# LB-word-topLevel.net
KiCad netlist of a schematic drawn in Altium Designer
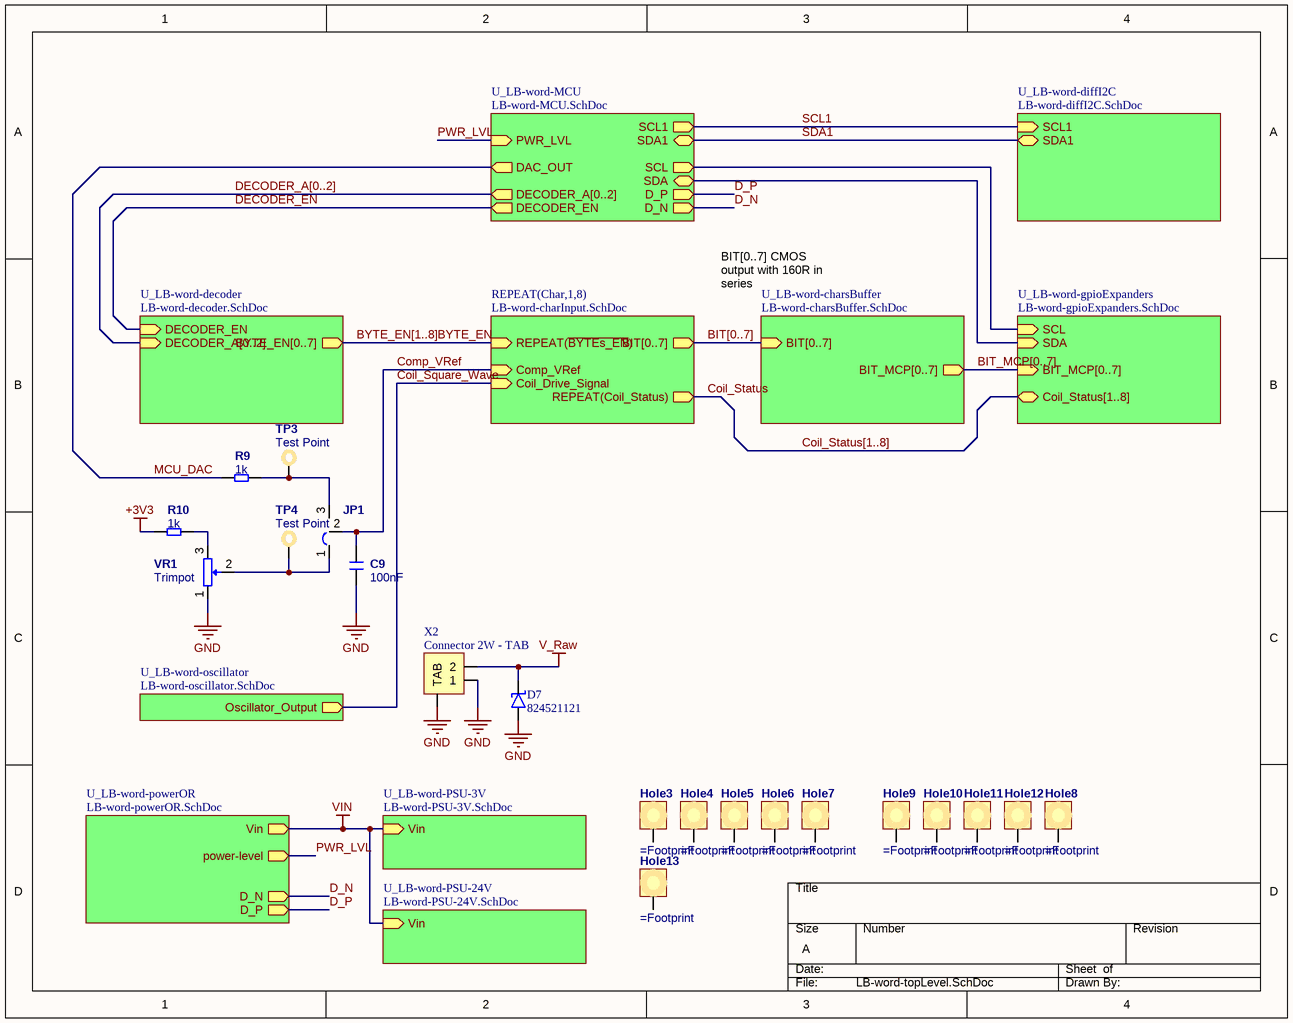
[diagram p0: LB-word-topLevel.SchDoc]

(export (version "E")
  (design (tool "Eeschema 10.0.6"))
  (components
    (comp (ref "C9")
      (value "100nF")
      (footprint "C0603_N")
      (description "Capacitor MLCC")
      (fields
        (field (name "MANUFACTURER") "Yageo")
        (field (name "MANUFACTURER PART NUMBER") "CC0603KRX7R9BB104")
      )
      (libsource (lib "wes") (part "Capacitor"))
    )
    (comp (ref "D7") (value "824521121") (footprint "DO214AC SMA") (libsource (lib "wes") (part "TVS")))
    (comp (ref "Hole3") (value "~") (footprint "M3 Plated Hole") (libsource (lib "wes") (part "Hole")))
    (comp (ref "Hole4") (value "~") (footprint "M3 Plated Hole") (libsource (lib "wes") (part "Hole")))
    (comp (ref "Hole5") (value "~") (footprint "M3 Plated Hole") (libsource (lib "wes") (part "Hole")))
    (comp (ref "Hole6") (value "~") (footprint "M3 Plated Hole") (libsource (lib "wes") (part "Hole")))
    (comp (ref "Hole7") (value "~") (footprint "M3 Plated Hole") (libsource (lib "wes") (part "Hole")))
    (comp (ref "Hole8") (value "~") (footprint "M3 Plated Hole") (libsource (lib "wes") (part "Hole")))
    (comp (ref "Hole9") (value "~") (footprint "M3 Plated Hole") (libsource (lib "wes") (part "Hole")))
    (comp (ref "Hole10") (value "~") (footprint "M3 Plated Hole") (libsource (lib "wes") (part "Hole")))
    (comp (ref "Hole11") (value "~") (footprint "M3 Plated Hole") (libsource (lib "wes") (part "Hole")))
    (comp (ref "Hole12") (value "~") (footprint "M3 Plated Hole") (libsource (lib "wes") (part "Hole")))
    (comp (ref "Hole13") (value "~") (footprint "M3 Plated Hole") (libsource (lib "wes") (part "Hole")))
    (comp (ref "JP1")
      (value "Jumper 3W")
      (footprint "Jumper SMD 3W NO")
      (libsource (lib "wes") (part "Jumper 3W"))
    )
    (comp (ref "R9")
      (value "1k")
      (footprint "R0603")
      (fields (field (name "PUBLISHER") "Altium Limited"))
      (libsource (lib "wes") (part "Resistor"))
    )
    (comp (ref "R10")
      (value "1k")
      (footprint "R0603")
      (fields (field (name "PUBLISHER") "Altium Limited"))
      (libsource (lib "wes") (part "Resistor"))
    )
    (comp (ref "TP3")
      (value "Test Point")
      (footprint "TestPoint-1.2mm")
      (libsource (lib "wes") (part "Test Point"))
    )
    (comp (ref "TP4")
      (value "Test Point")
      (footprint "TestPoint-1.2mm")
      (libsource (lib "wes") (part "Test Point"))
    )
    (comp (ref "VR1") (value "Trimpot") (footprint "Trimpot 3314") (libsource (lib "wes") (part "Trimpot")))
    (comp (ref "X2")
      (value "Connector 2W - TAB")
      (footprint "PTSM-2W-H-SMD")
      (libsource (lib "wes") (part "Connector 2W - TAB"))
    )
  )
  (nets
    (net (code "36") (name "+3V3") (class "Default")
      (node (ref "R10") (pin "1") (pinfunction "1_1") (pintype "passive"))
    )
    (net (code "44") (name "/Comp_VRef") (class "Default")
      (node (ref "C9") (pin "1") (pintype "passive"))
      (node (ref "JP1") (pin "2") (pinfunction "2_2") (pintype "passive"))
    )
    (net (code "49") (name "/MCU_DAC") (class "Default")
      (node (ref "R9") (pin "1") (pinfunction "1_1") (pintype "passive"))
    )
    (net (code "55") (name "GND") (class "Default")
      (node (ref "C9") (pin "2") (pintype "passive"))
      (node (ref "D7") (pin "A") (pinfunction "A_A") (pintype "passive"))
      (node (ref "VR1") (pin "1") (pinfunction "1_1") (pintype "passive"))
      (node (ref "X2") (pin "1") (pinfunction "1_1") (pintype "passive"))
      (node (ref "X2") (pin "TAB") (pinfunction "TAB_TAB") (pintype "power_in"))
    )
    (net (code "56") (name "Net-(JP1-Pad1)") (class "Default")
      (node (ref "JP1") (pin "1") (pinfunction "1_1") (pintype "passive"))
      (node (ref "TP4") (pin "1") (pinfunction "1_1") (pintype "passive"))
      (node (ref "VR1") (pin "2") (pinfunction "2_2") (pintype "passive"))
    )
    (net (code "57") (name "Net-(JP1-Pad3)") (class "Default")
      (node (ref "JP1") (pin "3") (pinfunction "3_3") (pintype "passive"))
      (node (ref "R9") (pin "2") (pinfunction "2_2") (pintype "passive"))
      (node (ref "TP3") (pin "1") (pinfunction "1_1") (pintype "passive"))
    )
    (net (code "58") (name "Net-(R10-Pad2)") (class "Default")
      (node (ref "R10") (pin "2") (pinfunction "2_2") (pintype "passive"))
      (node (ref "VR1") (pin "3") (pinfunction "3_3") (pintype "passive"))
    )
    (net (code "60") (name "V_Raw") (class "Default")
      (node (ref "D7") (pin "K") (pinfunction "K_K") (pintype "passive"))
      (node (ref "X2") (pin "2") (pinfunction "2_2") (pintype "passive"))
    )
    (net (code "61") (name "unconnected-(Hole3-Pad1)") (class "Default")
      (node (ref "Hole3") (pin "1") (pinfunction "1_1") (pintype "passive"))
    )
    (net (code "62") (name "unconnected-(Hole4-Pad1)") (class "Default")
      (node (ref "Hole4") (pin "1") (pinfunction "1_1") (pintype "passive"))
    )
    (net (code "63") (name "unconnected-(Hole5-Pad1)") (class "Default")
      (node (ref "Hole5") (pin "1") (pinfunction "1_1") (pintype "passive"))
    )
    (net (code "64") (name "unconnected-(Hole6-Pad1)") (class "Default")
      (node (ref "Hole6") (pin "1") (pinfunction "1_1") (pintype "passive"))
    )
    (net (code "65") (name "unconnected-(Hole7-Pad1)") (class "Default")
      (node (ref "Hole7") (pin "1") (pinfunction "1_1") (pintype "passive"))
    )
    (net (code "66") (name "unconnected-(Hole8-Pad1)") (class "Default")
      (node (ref "Hole8") (pin "1") (pinfunction "1_1") (pintype "passive"))
    )
    (net (code "67") (name "unconnected-(Hole9-Pad1)") (class "Default")
      (node (ref "Hole9") (pin "1") (pinfunction "1_1") (pintype "passive"))
    )
    (net (code "68") (name "unconnected-(Hole10-Pad1)") (class "Default")
      (node (ref "Hole10") (pin "1") (pinfunction "1_1") (pintype "passive"))
    )
    (net (code "69") (name "unconnected-(Hole11-Pad1)") (class "Default")
      (node (ref "Hole11") (pin "1") (pinfunction "1_1") (pintype "passive"))
    )
    (net (code "70") (name "unconnected-(Hole12-Pad1)") (class "Default")
      (node (ref "Hole12") (pin "1") (pinfunction "1_1") (pintype "passive"))
    )
    (net (code "71") (name "unconnected-(Hole13-Pad1)") (class "Default")
      (node (ref "Hole13") (pin "1") (pinfunction "1_1") (pintype "passive"))
    )
  )
)
